# tuya.net
KiCad netlist of a schematic drawn in Altium Designer
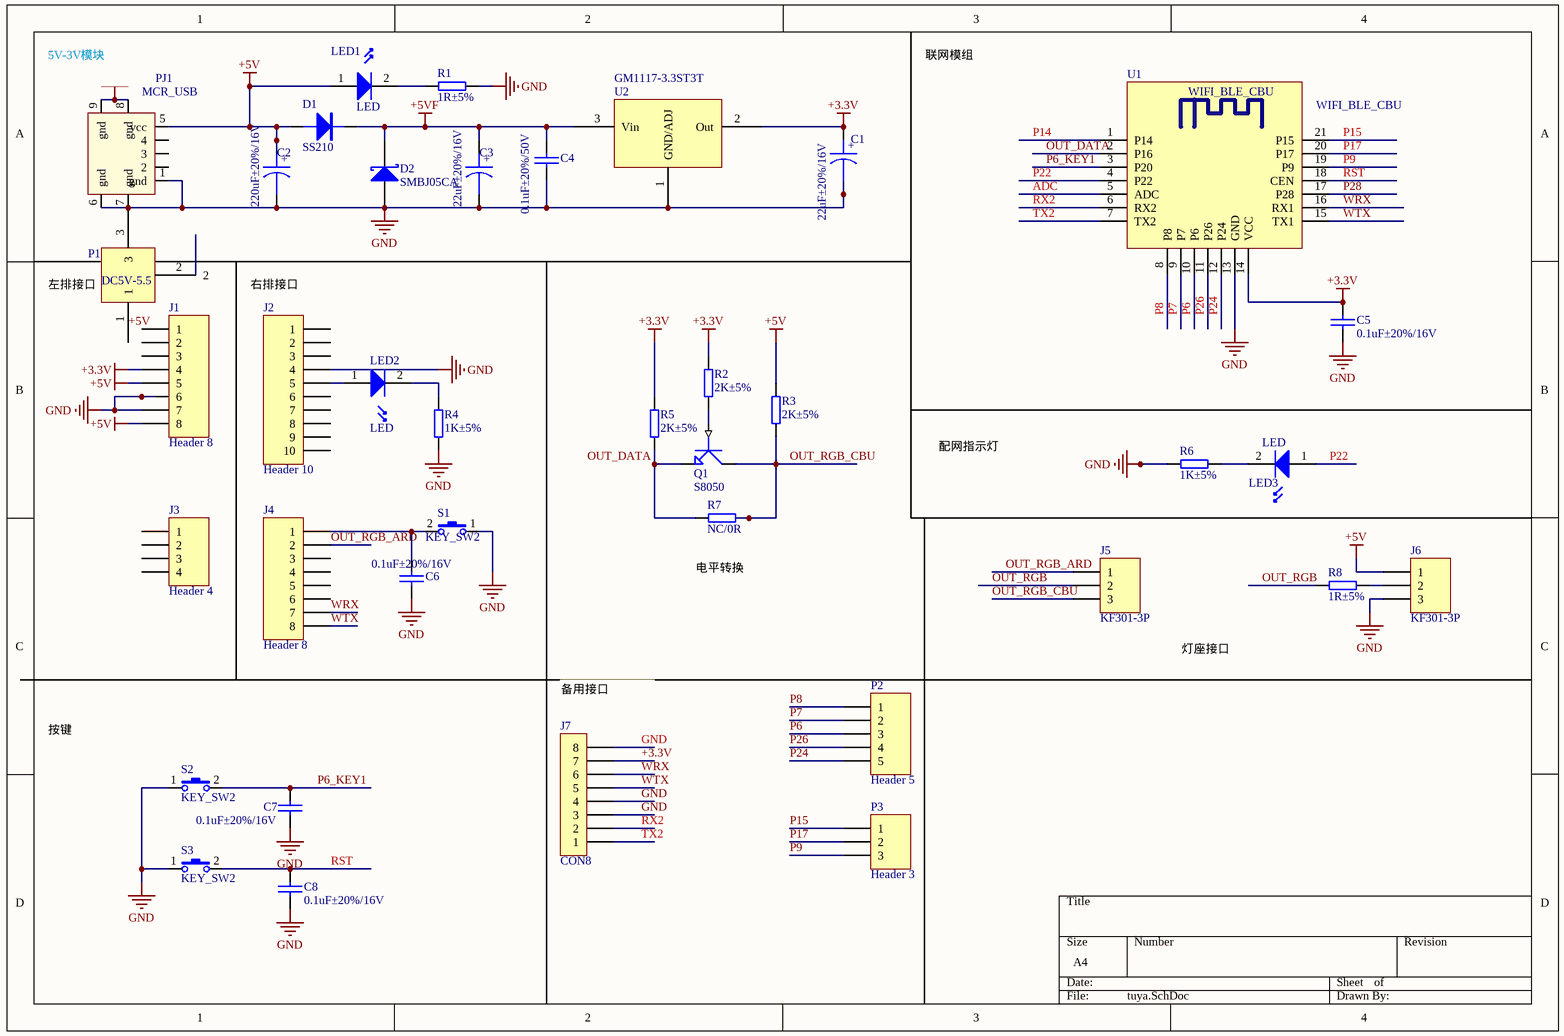
[diagram p0: tuya.SchDoc]

(export (version "E")
  (design (tool "Eeschema 10.0.6"))
  (components
    (comp (ref "C1")
      (value "22uF±20%/16V")
      (footprint "钽电容B3528")
      (description "Capacitor")
      (libsource (lib "*") (part "CAPACITOR POL"))
    )
    (comp (ref "C2")
      (value "220uF±20%/16V")
      (footprint "CD0.15")
      (description "Capacitor")
      (libsource (lib "*") (part "CAPACITOR POL"))
    )
    (comp (ref "C3")
      (value "22uF±20%/16V")
      (footprint "钽电容B3528")
      (description "Capacitor")
      (libsource (lib "*") (part "CAPACITOR POL"))
    )
    (comp (ref "C4")
      (value "0.1uF±20%/50V")
      (footprint "C0603")
      (description "Capacitor")
      (libsource (lib "昊华元件库sch") (part "CAP"))
    )
    (comp (ref "C5")
      (value "0.1uF±20%/16V")
      (footprint "C0603")
      (description "Capacitor")
      (libsource (lib "昊华元件库sch") (part "CAP"))
    )
    (comp (ref "C6")
      (value "0.1uF±20%/16V")
      (footprint "C0603")
      (description "Capacitor")
      (libsource (lib "昊华元件库sch") (part "CAP"))
    )
    (comp (ref "C7")
      (value "0.1uF±20%/16V")
      (footprint "C0603")
      (description "Capacitor")
      (libsource (lib "昊华元件库sch") (part "CAP"))
    )
    (comp (ref "C8")
      (value "0.1uF±20%/16V")
      (footprint "C0603")
      (description "Capacitor")
      (libsource (lib "昊华元件库sch") (part "CAP"))
    )
    (comp (ref "D1")
      (value "SS210")
      (footprint "SMA(DO-214AC)")
      (description "Diode")
      (libsource (lib "小马元件库sch") (part "Diode1"))
    )
    (comp (ref "D2")
      (value "SMBJ05CA")
      (footprint "SMB(DO-214AA)")
      (description "Schottky Diode")
      (fields (field (name "MFR") "Toshiba"))
      (libsource (lib "Miscellaneous Devices") (part "D Schottky"))
    )
    (comp (ref "J1")
      (value "Header 8")
      (footprint "HDR1X8")
      (description "Header, 8-Pin")
      (fields (field (name "PUBLISHER") "Altium Limited"))
      (libsource (lib "Miscellaneous Connectors") (part "Header 8"))
    )
    (comp (ref "J2")
      (value "Header 10")
      (footprint "HDR1X10")
      (description "Header, 10-Pin")
      (fields (field (name "PUBLISHER") "Altium Limited"))
      (libsource (lib "Miscellaneous Connectors") (part "Header 10"))
    )
    (comp (ref "J3")
      (value "Header 4")
      (footprint "HDR1X4")
      (description "Header, 4-Pin")
      (fields (field (name "PUBLISHER") "Altium Limited"))
      (libsource (lib "Miscellaneous Connectors") (part "Header 4"))
    )
    (comp (ref "J4")
      (value "Header 8")
      (footprint "HDR1X8")
      (description "Header, 8-Pin")
      (fields (field (name "PUBLISHER") "Altium Limited"))
      (libsource (lib "") (part "Header 8_1"))
    )
    (comp (ref "J5")
      (value "KF301-3P")
      (footprint "HDR1X3")
      (description "Header, 3-Pin")
      (fields (field (name "PUBLISHER") "Altium Limited"))
      (libsource (lib "Miscellaneous Connectors") (part "Header 3"))
    )
    (comp (ref "J6")
      (value "KF301-3P")
      (footprint "HDR1X3")
      (description "Header, 3-Pin")
      (fields (field (name "PUBLISHER") "Altium Limited"))
      (libsource (lib "Miscellaneous Connectors") (part "Header 3"))
    )
    (comp (ref "J7")
      (value "CON8")
      (footprint "HDR1X8Z")
      (description "Connector")
      (libsource (lib "小马元件库sch") (part "CON8"))
    )
    (comp (ref "LED1")
      (value "LED")
      (footprint "LED0805_1")
      (fields (field (name "PUBLISHER") "*"))
      (libsource (lib "小马元件库sch") (part "LED"))
    )
    (comp (ref "LED2")
      (value "LED")
      (footprint "LED0805_1")
      (fields (field (name "PUBLISHER") "*"))
      (libsource (lib "小马元件库sch") (part "LED"))
    )
    (comp (ref "LED3")
      (value "LED")
      (footprint "LED0805_1")
      (fields (field (name "PUBLISHER") "*"))
      (libsource (lib "小马元件库sch") (part "LED"))
    )
    (comp (ref "P1")
      (value "DC5V-5.5")
      (footprint "3pin-dc5-x")
      (libsource (lib "5v-dc5.5") (part "DC5V-5.5"))
    )
    (comp (ref "P2")
      (value "Header 5")
      (footprint "HDR1X5")
      (description "Header, 5-Pin")
      (fields (field (name "PUBLISHER") "Altium Limited"))
      (libsource (lib "Miscellaneous Connectors") (part "Header 5"))
    )
    (comp (ref "P3")
      (value "Header 3")
      (footprint "HDR1X3")
      (description "Header, 3-Pin")
      (fields (field (name "PUBLISHER") "Altium Limited"))
      (libsource (lib "Miscellaneous Connectors") (part "Header 3"))
    )
    (comp (ref "PJ1")
      (value "MCR_USB")
      (footprint "MICRO_USB-NEW-16.12.12")
      (fields (field (name "PUBLISHER") "*"))
      (libsource (lib "昊华元件库sch") (part "MCR_USB"))
    )
    (comp (ref "Q1")
      (value "S8050")
      (footprint "SOT-23-NPN")
      (description "NPN Transistor")
      (libsource (lib "小马元件库sch") (part "NPN"))
    )
    (comp (ref "R1") (value "1R±5%") (footprint "R0603") (libsource (lib "昊华元件库sch") (part "RES5")))
    (comp (ref "R2") (value "2K±5%") (footprint "R0603") (libsource (lib "昊华元件库sch") (part "RES5")))
    (comp (ref "R3") (value "2K±5%") (footprint "R0603") (libsource (lib "昊华元件库sch") (part "RES5")))
    (comp (ref "R4") (value "1K±5%") (footprint "R0603") (libsource (lib "昊华元件库sch") (part "RES5")))
    (comp (ref "R5") (value "2K±5%") (footprint "R0603") (libsource (lib "昊华元件库sch") (part "RES5")))
    (comp (ref "R6") (value "1K±5%") (footprint "R0603") (libsource (lib "昊华元件库sch") (part "RES5")))
    (comp (ref "R7") (value "NC/0R") (footprint "R0603") (libsource (lib "昊华元件库sch") (part "RES5")))
    (comp (ref "R8") (value "1R±5%") (footprint "R0603") (libsource (lib "昊华元件库sch") (part "RES5")))
    (comp (ref "S1") (value "KEY_SW2") (footprint "KEY4-SMD") (libsource (lib "小马元件库sch") (part "KEY_SW2")))
    (comp (ref "S2") (value "KEY_SW2") (footprint "KEY4-SMD") (libsource (lib "小马元件库sch") (part "KEY_SW2")))
    (comp (ref "S3") (value "KEY_SW2") (footprint "KEY4-SMD") (libsource (lib "小马元件库sch") (part "KEY_SW2")))
    (comp (ref "U1")
      (value "WIFI_BLE_CBU")
      (footprint "WIFI_BLE_CBU")
      (description "Module")
      (libsource (lib "TYModeSchlib V03") (part "WIFI_BLE_CBU"))
    )
    (comp (ref "U2") (value "GM1117-3.3ST3T") (footprint "SOT-223") (libsource (lib "mylib") (part "GM1117")))
  )
  (nets
    (net (code "1") (name "+3.3V") (class "Default")
      (node (ref "C1") (pin "1") (pinfunction "1_1") (pintype "passive"))
      (node (ref "C5") (pin "2") (pinfunction "2_2") (pintype "passive"))
      (node (ref "J1") (pin "4") (pinfunction "4_4") (pintype "passive"))
      (node (ref "J7") (pin "7") (pinfunction "7_7") (pintype "passive"))
      (node (ref "R2") (pin "1") (pinfunction "1_1") (pintype "passive"))
      (node (ref "R5") (pin "1") (pinfunction "1_1") (pintype "passive"))
      (node (ref "U1") (pin "14") (pinfunction "VCC_14") (pintype "passive"))
      (node (ref "U2") (pin "2") (pinfunction "Out_2") (pintype "passive"))
    )
    (net (code "2") (name "+5V") (class "Default")
      (node (ref "C2") (pin "1") (pinfunction "1_1") (pintype "passive"))
      (node (ref "D1") (pin "1") (pinfunction "1_1") (pintype "passive"))
      (node (ref "J1") (pin "5") (pinfunction "5_5") (pintype "passive"))
      (node (ref "J1") (pin "8") (pinfunction "8_8") (pintype "passive"))
      (node (ref "J6") (pin "1") (pinfunction "1_1") (pintype "passive"))
      (node (ref "LED1") (pin "1") (pinfunction "1_1") (pintype "passive"))
      (node (ref "PJ1") (pin "5") (pinfunction "vcc_5") (pintype "passive"))
      (node (ref "R3") (pin "1") (pinfunction "1_1") (pintype "passive"))
    )
    (net (code "3") (name "+5VF") (class "Default")
      (node (ref "C3") (pin "1") (pinfunction "1_1") (pintype "passive"))
      (node (ref "C4") (pin "1") (pinfunction "1_1") (pintype "passive"))
      (node (ref "D1") (pin "2") (pinfunction "2_2") (pintype "passive"))
      (node (ref "D2") (pin "2") (pinfunction "K_2") (pintype "passive"))
      (node (ref "U2") (pin "3") (pinfunction "Vin_3") (pintype "passive"))
    )
    (net (code "5") (name "/ADC") (class "Default")
      (node (ref "U1") (pin "5") (pinfunction "ADC_5") (pintype "passive"))
    )
    (net (code "6") (name "/OUT_DATA") (class "Default")
      (node (ref "U1") (pin "2") (pinfunction "P16_2") (pintype "passive"))
    )
    (net (code "7") (name "/OUT_RGB") (class "Default")
      (node (ref "J5") (pin "2") (pinfunction "2_2") (pintype "passive"))
      (node (ref "R8") (pin "1") (pinfunction "1_1") (pintype "passive"))
    )
    (net (code "8") (name "/OUT_RGB_ARD") (class "Default")
      (node (ref "J4") (pin "2") (pinfunction "2_2") (pintype "passive"))
      (node (ref "J5") (pin "1") (pinfunction "1_1") (pintype "passive"))
    )
    (net (code "9") (name "/OUT_RGB_CBU") (class "Default")
      (node (ref "J5") (pin "3") (pinfunction "3_3") (pintype "passive"))
      (node (ref "Q1") (pin "3") (pinfunction "C_3") (pintype "passive"))
      (node (ref "R3") (pin "2") (pinfunction "2_2") (pintype "passive"))
      (node (ref "R7") (pin "2") (pinfunction "2_2") (pintype "passive"))
    )
    (net (code "10") (name "/P6") (class "Default")
      (node (ref "P2") (pin "3") (pinfunction "3_3") (pintype "passive"))
      (node (ref "U1") (pin "10") (pinfunction "P6_10") (pintype "passive"))
    )
    (net (code "11") (name "/P6_KEY1") (class "Default")
      (node (ref "C7") (pin "2") (pinfunction "2_2") (pintype "passive"))
      (node (ref "S2") (pin "2") (pinfunction "2_2") (pintype "passive"))
      (node (ref "U1") (pin "3") (pinfunction "P20_3") (pintype "passive"))
    )
    (net (code "12") (name "/P7") (class "Default")
      (node (ref "P2") (pin "2") (pinfunction "2_2") (pintype "passive"))
      (node (ref "U1") (pin "9") (pinfunction "P7_9") (pintype "passive"))
    )
    (net (code "13") (name "/P8") (class "Default")
      (node (ref "P2") (pin "1") (pinfunction "1_1") (pintype "passive"))
      (node (ref "U1") (pin "8") (pinfunction "P8_8") (pintype "passive"))
    )
    (net (code "14") (name "/P9") (class "Default")
      (node (ref "P3") (pin "3") (pinfunction "3_3") (pintype "passive"))
      (node (ref "U1") (pin "19") (pinfunction "P9_19") (pintype "passive"))
    )
    (net (code "15") (name "/P14") (class "Default")
      (node (ref "U1") (pin "1") (pinfunction "P14_1") (pintype "passive"))
    )
    (net (code "16") (name "/P15") (class "Default")
      (node (ref "P3") (pin "1") (pinfunction "1_1") (pintype "passive"))
      (node (ref "U1") (pin "21") (pinfunction "P15_21") (pintype "passive"))
    )
    (net (code "17") (name "/P17") (class "Default")
      (node (ref "P3") (pin "2") (pinfunction "2_2") (pintype "passive"))
      (node (ref "U1") (pin "20") (pinfunction "P17_20") (pintype "passive"))
    )
    (net (code "18") (name "/P22") (class "Default")
      (node (ref "LED3") (pin "1") (pinfunction "1_1") (pintype "passive"))
      (node (ref "U1") (pin "4") (pinfunction "P22_4") (pintype "passive"))
    )
    (net (code "19") (name "/P24") (class "Default")
      (node (ref "P2") (pin "5") (pinfunction "5_5") (pintype "passive"))
      (node (ref "U1") (pin "12") (pinfunction "P24_12") (pintype "passive"))
    )
    (net (code "20") (name "/P26") (class "Default")
      (node (ref "P2") (pin "4") (pinfunction "4_4") (pintype "passive"))
      (node (ref "U1") (pin "11") (pinfunction "P26_11") (pintype "passive"))
    )
    (net (code "21") (name "/P28") (class "Default")
      (node (ref "U1") (pin "17") (pinfunction "P28_17") (pintype "passive"))
    )
    (net (code "22") (name "/RST") (class "Default")
      (node (ref "C8") (pin "1") (pinfunction "1_1") (pintype "passive"))
      (node (ref "S3") (pin "2") (pinfunction "2_2") (pintype "passive"))
      (node (ref "U1") (pin "18") (pinfunction "CEN_18") (pintype "passive"))
    )
    (net (code "23") (name "/RX2") (class "Default")
      (node (ref "J7") (pin "2") (pinfunction "2_2") (pintype "passive"))
      (node (ref "U1") (pin "6") (pinfunction "RX2_6") (pintype "passive"))
    )
    (net (code "24") (name "/TX2") (class "Default")
      (node (ref "J7") (pin "1") (pinfunction "1_1") (pintype "passive"))
      (node (ref "U1") (pin "7") (pinfunction "TX2_7") (pintype "passive"))
    )
    (net (code "25") (name "/WRX") (class "Default")
      (node (ref "J4") (pin "7") (pinfunction "7_7") (pintype "passive"))
      (node (ref "J7") (pin "6") (pinfunction "6_6") (pintype "passive"))
      (node (ref "U1") (pin "16") (pinfunction "RX1_16") (pintype "passive"))
    )
    (net (code "26") (name "/WTX") (class "Default")
      (node (ref "J4") (pin "8") (pinfunction "8_8") (pintype "passive"))
      (node (ref "J7") (pin "5") (pinfunction "5_5") (pintype "passive"))
      (node (ref "U1") (pin "15") (pinfunction "TX1_15") (pintype "passive"))
    )
    (net (code "27") (name "GND") (class "Default")
      (node (ref "C1") (pin "2") (pinfunction "2_2") (pintype "passive"))
      (node (ref "C2") (pin "2") (pinfunction "2_2") (pintype "passive"))
      (node (ref "C3") (pin "2") (pinfunction "2_2") (pintype "passive"))
      (node (ref "C4") (pin "2") (pinfunction "2_2") (pintype "passive"))
      (node (ref "C5") (pin "1") (pinfunction "1_1") (pintype "passive"))
      (node (ref "C6") (pin "1") (pinfunction "1_1") (pintype "passive"))
      (node (ref "C7") (pin "1") (pinfunction "1_1") (pintype "passive"))
      (node (ref "C8") (pin "2") (pinfunction "2_2") (pintype "passive"))
      (node (ref "D2") (pin "1") (pinfunction "A_1") (pintype "passive"))
      (node (ref "J1") (pin "6") (pinfunction "6_6") (pintype "passive"))
      (node (ref "J1") (pin "7") (pinfunction "7_7") (pintype "passive"))
      (node (ref "J2") (pin "4") (pinfunction "4_4") (pintype "passive"))
      (node (ref "J6") (pin "3") (pinfunction "3_3") (pintype "passive"))
      (node (ref "J7") (pin "3") (pinfunction "3_3") (pintype "passive"))
      (node (ref "J7") (pin "4") (pinfunction "4_4") (pintype "passive"))
      (node (ref "J7") (pin "8") (pinfunction "8_8") (pintype "passive"))
      (node (ref "P1") (pin "3") (pinfunction "3_3") (pintype "power_in"))
      (node (ref "PJ1") (pin "1") (pinfunction "gnd_1") (pintype "passive"))
      (node (ref "PJ1") (pin "6") (pinfunction "gnd_6") (pintype "passive"))
      (node (ref "PJ1") (pin "7") (pinfunction "gnd_7") (pintype "passive"))
      (node (ref "PJ1") (pin "8") (pinfunction "gnd_8") (pintype "passive"))
      (node (ref "PJ1") (pin "9") (pinfunction "gnd_9") (pintype "passive"))
      (node (ref "R1") (pin "2") (pinfunction "2_2") (pintype "passive"))
      (node (ref "R4") (pin "1") (pinfunction "1_1") (pintype "passive"))
      (node (ref "R6") (pin "2") (pinfunction "2_2") (pintype "passive"))
      (node (ref "S1") (pin "1") (pinfunction "1_1") (pintype "passive"))
      (node (ref "S2") (pin "1") (pinfunction "1_1") (pintype "passive"))
      (node (ref "S3") (pin "1") (pinfunction "1_1") (pintype "passive"))
      (node (ref "U1") (pin "13") (pinfunction "GND_13") (pintype "passive"))
      (node (ref "U2") (pin "1") (pinfunction "GND/ADJ_1") (pintype "passive"))
    )
    (net (code "28") (name "Net-(C6-Pad2)") (class "Default")
      (node (ref "C6") (pin "2") (pinfunction "2_2") (pintype "passive"))
      (node (ref "J4") (pin "1") (pinfunction "1_1") (pintype "passive"))
      (node (ref "S1") (pin "2") (pinfunction "2_2") (pintype "passive"))
    )
    (net (code "29") (name "Net-(J2-Pad5)") (class "Default")
      (node (ref "J2") (pin "5") (pinfunction "5_5") (pintype "passive"))
      (node (ref "LED2") (pin "1") (pinfunction "1_1") (pintype "passive"))
    )
    (net (code "30") (name "Net-(J6-Pad2)") (class "Default")
      (node (ref "J6") (pin "2") (pinfunction "2_2") (pintype "passive"))
      (node (ref "R8") (pin "2") (pinfunction "2_2") (pintype "passive"))
    )
    (net (code "31") (name "Net-(LED1-Pad2)") (class "Default")
      (node (ref "LED1") (pin "2") (pinfunction "2_2") (pintype "passive"))
      (node (ref "R1") (pin "1") (pinfunction "1_1") (pintype "passive"))
    )
    (net (code "32") (name "Net-(LED2-Pad2)") (class "Default")
      (node (ref "LED2") (pin "2") (pinfunction "2_2") (pintype "passive"))
      (node (ref "R4") (pin "2") (pinfunction "2_2") (pintype "passive"))
    )
    (net (code "33") (name "Net-(LED3-Pad2)") (class "Default")
      (node (ref "LED3") (pin "2") (pinfunction "2_2") (pintype "passive"))
      (node (ref "R6") (pin "1") (pinfunction "1_1") (pintype "passive"))
    )
    (net (code "34") (name "Net-(Q1-B)") (class "Default")
      (node (ref "Q1") (pin "2") (pinfunction "B_2") (pintype "input"))
      (node (ref "R2") (pin "2") (pinfunction "2_2") (pintype "passive"))
    )
    (net (code "35") (name "Net-(Q1-E)") (class "Default")
      (node (ref "Q1") (pin "1") (pinfunction "E_1") (pintype "passive"))
      (node (ref "R5") (pin "2") (pinfunction "2_2") (pintype "passive"))
      (node (ref "R7") (pin "1") (pinfunction "1_1") (pintype "passive"))
    )
    (net (code "36") (name "unconnected-(J1-Pad1)") (class "Default")
      (node (ref "J1") (pin "1") (pinfunction "1_1") (pintype "passive"))
    )
    (net (code "37") (name "unconnected-(J1-Pad2)") (class "Default")
      (node (ref "J1") (pin "2") (pinfunction "2_2") (pintype "passive"))
    )
    (net (code "38") (name "unconnected-(J1-Pad3)") (class "Default")
      (node (ref "J1") (pin "3") (pinfunction "3_3") (pintype "passive"))
    )
    (net (code "39") (name "unconnected-(J2-Pad1)") (class "Default")
      (node (ref "J2") (pin "1") (pinfunction "1_1") (pintype "passive"))
    )
    (net (code "40") (name "unconnected-(J2-Pad2)") (class "Default")
      (node (ref "J2") (pin "2") (pinfunction "2_2") (pintype "passive"))
    )
    (net (code "41") (name "unconnected-(J2-Pad3)") (class "Default")
      (node (ref "J2") (pin "3") (pinfunction "3_3") (pintype "passive"))
    )
    (net (code "42") (name "unconnected-(J2-Pad6)") (class "Default")
      (node (ref "J2") (pin "6") (pinfunction "6_6") (pintype "passive"))
    )
    (net (code "43") (name "unconnected-(J2-Pad7)") (class "Default")
      (node (ref "J2") (pin "7") (pinfunction "7_7") (pintype "passive"))
    )
    (net (code "44") (name "unconnected-(J2-Pad8)") (class "Default")
      (node (ref "J2") (pin "8") (pinfunction "8_8") (pintype "passive"))
    )
    (net (code "45") (name "unconnected-(J2-Pad9)") (class "Default")
      (node (ref "J2") (pin "9") (pinfunction "9_9") (pintype "passive"))
    )
    (net (code "46") (name "unconnected-(J2-Pad10)") (class "Default")
      (node (ref "J2") (pin "10") (pinfunction "10_10") (pintype "passive"))
    )
    (net (code "47") (name "unconnected-(J3-Pad1)") (class "Default")
      (node (ref "J3") (pin "1") (pinfunction "1_1") (pintype "passive"))
    )
    (net (code "48") (name "unconnected-(J3-Pad2)") (class "Default")
      (node (ref "J3") (pin "2") (pinfunction "2_2") (pintype "passive"))
    )
    (net (code "49") (name "unconnected-(J3-Pad3)") (class "Default")
      (node (ref "J3") (pin "3") (pinfunction "3_3") (pintype "passive"))
    )
    (net (code "50") (name "unconnected-(J3-Pad4)") (class "Default")
      (node (ref "J3") (pin "4") (pinfunction "4_4") (pintype "passive"))
    )
    (net (code "51") (name "unconnected-(J4-Pad3)") (class "Default")
      (node (ref "J4") (pin "3") (pinfunction "3_3") (pintype "passive"))
    )
    (net (code "52") (name "unconnected-(J4-Pad4)") (class "Default")
      (node (ref "J4") (pin "4") (pinfunction "4_4") (pintype "passive"))
    )
    (net (code "53") (name "unconnected-(J4-Pad5)") (class "Default")
      (node (ref "J4") (pin "5") (pinfunction "5_5") (pintype "passive"))
    )
    (net (code "54") (name "unconnected-(J4-Pad6)") (class "Default")
      (node (ref "J4") (pin "6") (pinfunction "6_6") (pintype "passive"))
    )
    (net (code "55") (name "unconnected-(P1-Pad1)") (class "Default")
      (node (ref "P1") (pin "1") (pinfunction "1_1") (pintype "power_in"))
    )
    (net (code "56") (name "unconnected-(P1-Pad2)") (class "Default")
      (node (ref "P1") (pin "2") (pinfunction "2_2") (pintype "power_in"))
    )
    (net (code "57") (name "unconnected-(PJ1-Pad2)") (class "Default")
      (node (ref "PJ1") (pin "2") (pinfunction "2_2") (pintype "passive"))
    )
    (net (code "58") (name "unconnected-(PJ1-Pad3)") (class "Default")
      (node (ref "PJ1") (pin "3") (pinfunction "3_3") (pintype "passive"))
    )
    (net (code "59") (name "unconnected-(PJ1-Pad4)") (class "Default")
      (node (ref "PJ1") (pin "4") (pinfunction "4_4") (pintype "passive"))
    )
  )
)
